# MPeV6.net
KiCad netlist of a schematic drawn in EAGLE
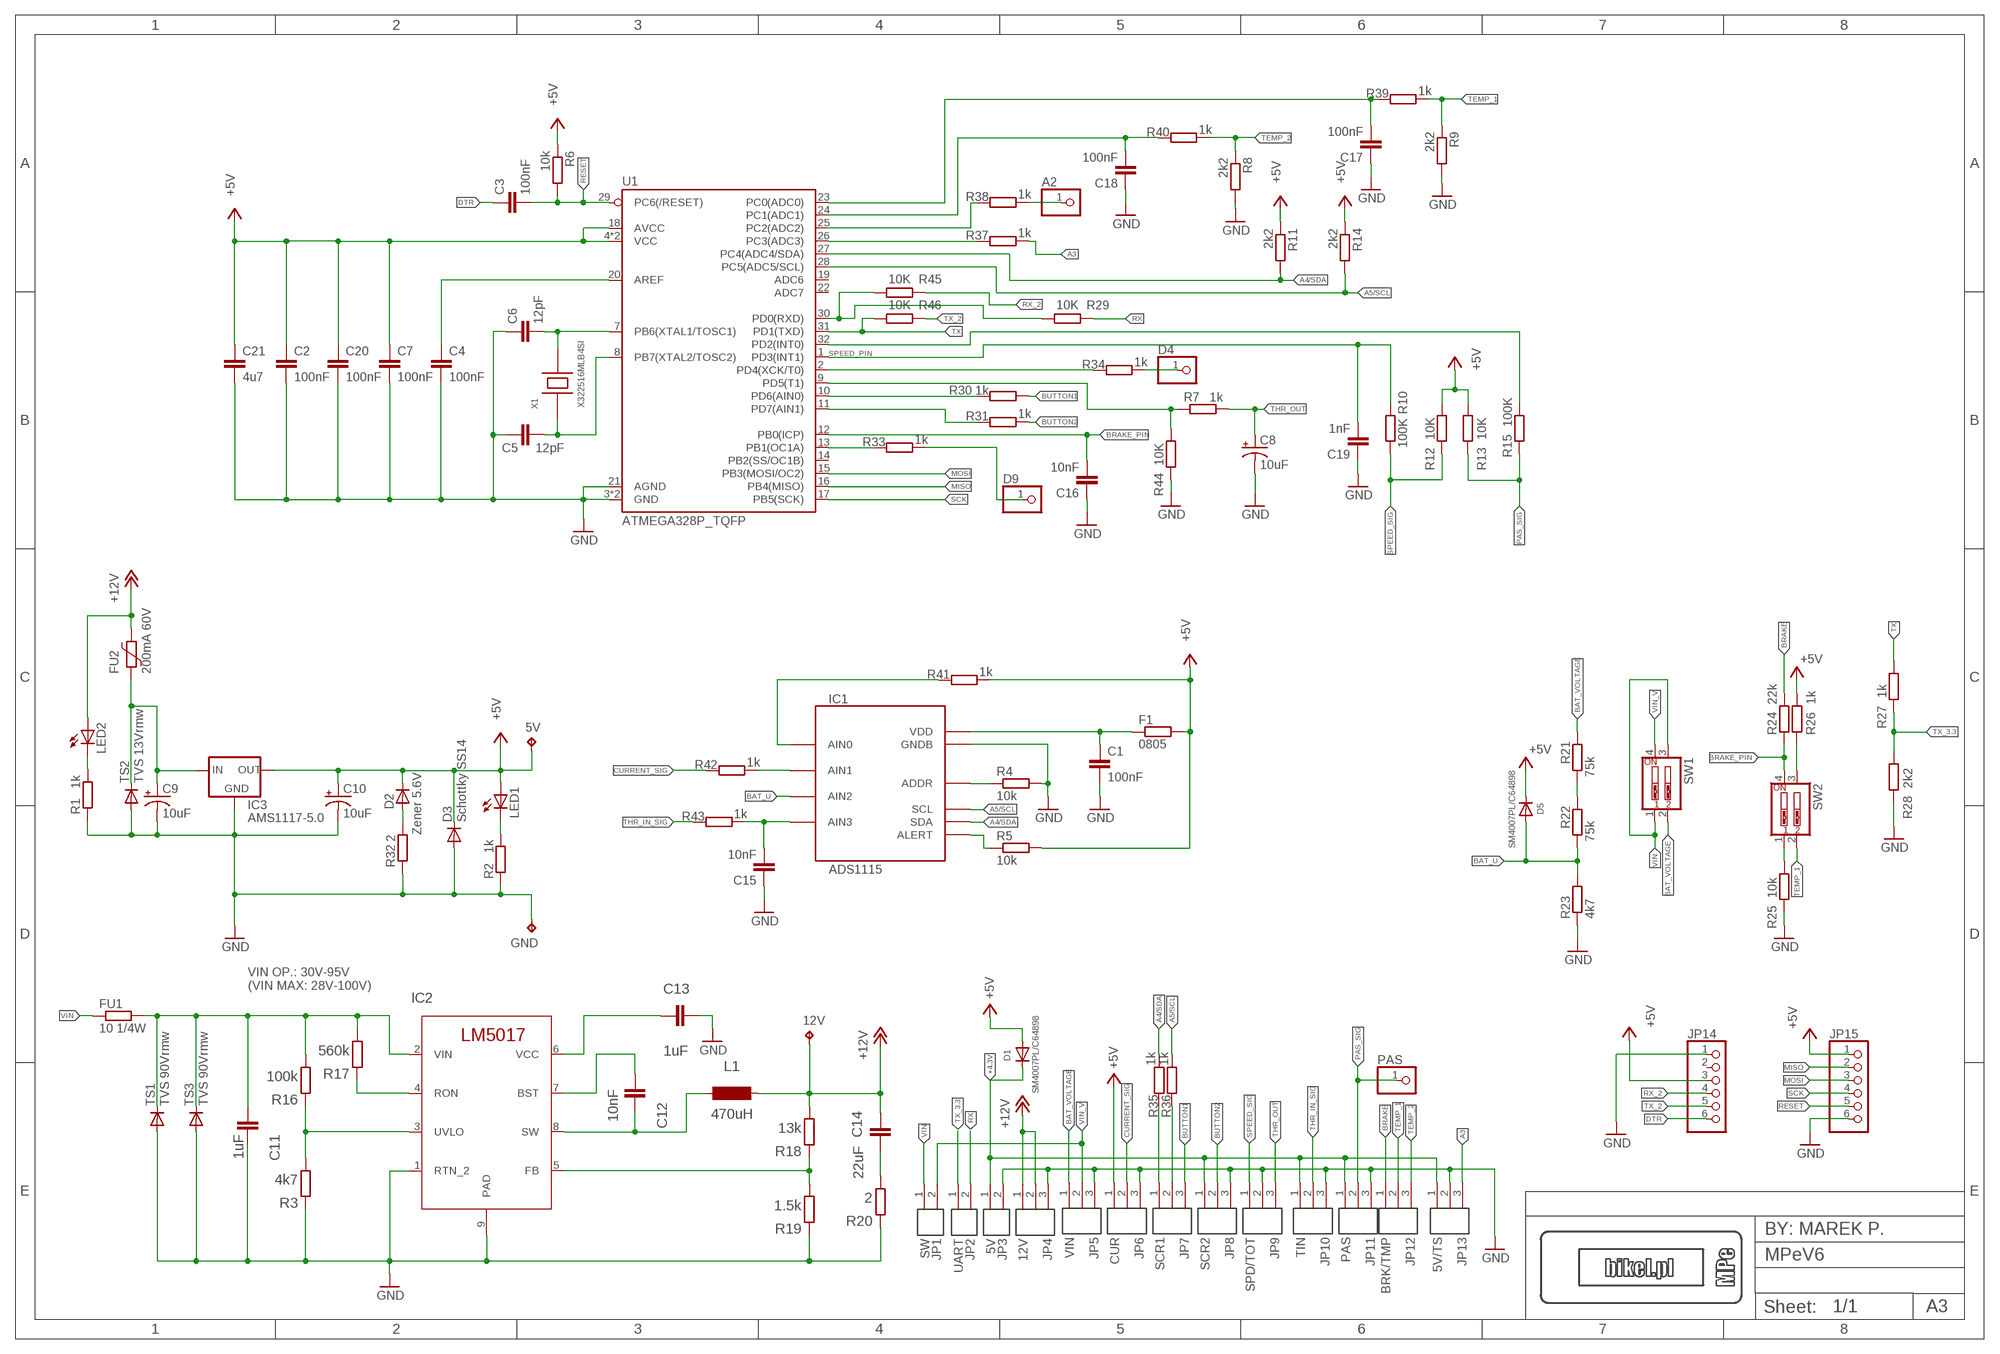
[diagram p0: schematic, sheet 1]

(export (version "E")
  (design (tool "Eeschema 10.0.6"))
  (components
    (comp (ref "5V")
      (value "TP_5V")
      (footprint "eagle-import:P1-13")
      (libsource (lib "eagle-import") (part "TPPAD1-13"))
    )
    (comp (ref "12V")
      (value "TP_5V")
      (footprint "eagle-import:P1-13")
      (libsource (lib "eagle-import") (part "TPPAD1-13"))
    )
    (comp (ref "A2")
      (value "PINHD-1X1")
      (footprint "eagle-import:1X01")
      (libsource (lib "eagle-import") (part "PINHD-1X1"))
    )
    (comp (ref "C1")
      (value "100nF")
      (footprint "eagle-import:C0603")
      (libsource (lib "eagle-import") (part "C-EUC0603"))
    )
    (comp (ref "C2")
      (value "100nF")
      (footprint "eagle-import:C0603")
      (libsource (lib "eagle-import") (part "C-EUC0603"))
    )
    (comp (ref "C3")
      (value "100nF")
      (footprint "eagle-import:C0603")
      (libsource (lib "eagle-import") (part "C-EUC0603"))
    )
    (comp (ref "C4")
      (value "100nF")
      (footprint "eagle-import:C0603")
      (libsource (lib "eagle-import") (part "C-EUC0603"))
    )
    (comp (ref "C5")
      (value "12pF")
      (footprint "eagle-import:C0603")
      (libsource (lib "eagle-import") (part "C-EUC0603"))
    )
    (comp (ref "C6")
      (value "12pF")
      (footprint "eagle-import:C0603")
      (libsource (lib "eagle-import") (part "C-EUC0603"))
    )
    (comp (ref "C7")
      (value "100nF")
      (footprint "eagle-import:C0603")
      (libsource (lib "eagle-import") (part "C-EUC0603"))
    )
    (comp (ref "C8")
      (value "10uF")
      (footprint "eagle-import:EIA3216")
      (libsource (lib "eagle-import") (part "10UF-POLAR-EIA3216-16V-10%(TANT)"))
    )
    (comp (ref "C9")
      (value "10uF")
      (footprint "eagle-import:EIA3216")
      (libsource (lib "eagle-import") (part "10UF-POLAR-EIA3216-16V-10%(TANT)"))
    )
    (comp (ref "C10")
      (value "10uF")
      (footprint "eagle-import:EIA3216")
      (libsource (lib "eagle-import") (part "10UF-POLAR-EIA3216-16V-10%(TANT)"))
    )
    (comp (ref "C11")
      (value "1uF")
      (footprint "eagle-import:C1206")
      (libsource (lib "eagle-import") (part "C-EUC1206"))
    )
    (comp (ref "C12")
      (value "10nF")
      (footprint "eagle-import:C0805")
      (libsource (lib "eagle-import") (part "C-EUC0805"))
    )
    (comp (ref "C13")
      (value "1uF")
      (footprint "eagle-import:C0603")
      (libsource (lib "eagle-import") (part "C-EUC0603"))
    )
    (comp (ref "C14")
      (value "22uF")
      (footprint "eagle-import:C0805")
      (libsource (lib "eagle-import") (part "C-EUC0805"))
    )
    (comp (ref "C15")
      (value "10nF")
      (footprint "eagle-import:C0603")
      (libsource (lib "eagle-import") (part "C-EUC0603"))
    )
    (comp (ref "C16")
      (value "10nF")
      (footprint "eagle-import:C0603")
      (libsource (lib "eagle-import") (part "C-EUC0603"))
    )
    (comp (ref "C17")
      (value "100nF")
      (footprint "eagle-import:C0603")
      (libsource (lib "eagle-import") (part "C-EUC0603"))
    )
    (comp (ref "C18")
      (value "100nF")
      (footprint "eagle-import:C0603")
      (libsource (lib "eagle-import") (part "C-EUC0603"))
    )
    (comp (ref "C19")
      (value "1nF")
      (footprint "eagle-import:C0603")
      (libsource (lib "eagle-import") (part "C-EUC0603"))
    )
    (comp (ref "C20")
      (value "100nF")
      (footprint "eagle-import:C0603")
      (libsource (lib "eagle-import") (part "C-EUC0603"))
    )
    (comp (ref "C21")
      (value "4u7")
      (footprint "eagle-import:C0603")
      (libsource (lib "eagle-import") (part "C-EUC0603"))
    )
    (comp (ref "D1")
      (value "SM4007PL/C64898")
      (footprint "eagle-import:SOD-123")
      (libsource (lib "eagle-import") (part "DIODESOD-123"))
    )
    (comp (ref "D2")
      (value "Zener 5.6V")
      (footprint "eagle-import:MELF-MLL34")
      (libsource (lib "eagle-import") (part "D-MLL-34"))
    )
    (comp (ref "D3")
      (value "Schottky SS14")
      (footprint "eagle-import:DO-214AC")
      (libsource (lib "eagle-import") (part "DIODE-DO-214AC"))
    )
    (comp (ref "D4")
      (value "PINHD-1X1")
      (footprint "eagle-import:1X01")
      (libsource (lib "eagle-import") (part "PINHD-1X1"))
    )
    (comp (ref "D5")
      (value "SM4007PL/C64898")
      (footprint "eagle-import:SOD-123")
      (libsource (lib "eagle-import") (part "DIODESOD-123"))
    )
    (comp (ref "D9")
      (value "PINHD-1X1")
      (footprint "eagle-import:1X01")
      (libsource (lib "eagle-import") (part "PINHD-1X1"))
    )
    (comp (ref "F1")
      (value "0805")
      (footprint "eagle-import:R0805")
      (libsource (lib "eagle-import") (part "R-EU_R0805"))
    )
    (comp (ref "FU1")
      (value "10 1/4W")
      (footprint "eagle-import:0204_7")
      (libsource (lib "eagle-import") (part "R-EU_0204/7"))
    )
    (comp (ref "FU2")
      (value "200mA 60V")
      (footprint "eagle-import:1812L")
      (fields (field (name "MF") "Littelfuse") (field (name "MPN") "1812L050/30"))
      (libsource (lib "eagle-import") (part "?1812L050/30"))
    )
    (comp (ref "GND")
      (value "TP_5V")
      (footprint "eagle-import:P1-13")
      (libsource (lib "eagle-import") (part "TPPAD1-13"))
    )
    (comp (ref "IC1")
      (value "ADS1115")
      (footprint "eagle-import:MSOP10_0.5")
      (libsource (lib "eagle-import") (part "ADS1015IDGT"))
    )
    (comp (ref "IC2")
      (value "LM5017MR/NOPB")
      (footprint "eagle-import:MRA08A")
      (fields (field (name "MANUFACTURER_PART_NUMBER") "LM5017MRNOPB"))
      (libsource (lib "eagle-import") (part "LM5017MR/NOPB"))
    )
    (comp (ref "IC3")
      (value "AMS1117-5.0")
      (footprint "eagle-import:SOT223")
      (fields (field (name "MF") "Texas Instruments") (field (name "MPN") "LM1117MP-5.0"))
      (libsource (lib "eagle-import") (part "LM1117?-MP5.0"))
    )
    (comp (ref "JP1")
      (value "SW")
      (footprint "eagle-import:ARK254-PB+")
      (libsource (lib "eagle-import") (part "ARK254-2PB+"))
    )
    (comp (ref "JP2")
      (value "UART")
      (footprint "eagle-import:ARK254-2-COM")
      (libsource (lib "eagle-import") (part "ARK254-2ARK254-2-COM"))
    )
    (comp (ref "JP3")
      (value "5V")
      (footprint "eagle-import:ARK254-2-5V")
      (libsource (lib "eagle-import") (part "ARK254-2ARK254-2-5V"))
    )
    (comp (ref "JP4")
      (value "12V")
      (footprint "eagle-import:ARK254-3-12V-EL")
      (libsource (lib "eagle-import") (part "ARK254-3ARK254-3-12V-EL"))
    )
    (comp (ref "JP5")
      (value "VIN")
      (footprint "eagle-import:ARK254-3-VIN")
      (libsource (lib "eagle-import") (part "ARK254-3ARK254-3-VIN"))
    )
    (comp (ref "JP6")
      (value "CUR")
      (footprint "eagle-import:ARK254-3+S-")
      (libsource (lib "eagle-import") (part "ARK254-3+S-"))
    )
    (comp (ref "JP7")
      (value "SCR1")
      (footprint "eagle-import:ARK254-3")
      (libsource (lib "eagle-import") (part "ARK254-3"))
    )
    (comp (ref "JP8")
      (value "SCR2")
      (footprint "eagle-import:ARK254-3")
      (libsource (lib "eagle-import") (part "ARK254-3"))
    )
    (comp (ref "JP9")
      (value "SPD/TOT")
      (footprint "eagle-import:ARK254-3-SPD-TOT")
      (libsource (lib "eagle-import") (part "ARK254-3ARK254-3-SPD-TOT"))
    )
    (comp (ref "JP10")
      (value "TIN")
      (footprint "eagle-import:ARK254-3+S-")
      (libsource (lib "eagle-import") (part "ARK254-3+S-"))
    )
    (comp (ref "JP11")
      (value "PAS")
      (footprint "eagle-import:ARK254-3+S-")
      (libsource (lib "eagle-import") (part "ARK254-3+S-"))
    )
    (comp (ref "JP12")
      (value "BRK/TMP")
      (footprint "eagle-import:ARK254-3-BRK-TMP")
      (libsource (lib "eagle-import") (part "ARK254-3ARK254-3-BRK-TMP"))
    )
    (comp (ref "JP13")
      (value "5V/TS")
      (footprint "eagle-import:ARK254-3-5V-TS")
      (libsource (lib "eagle-import") (part "ARK254-3ARK254-3-5V-TS"))
    )
    (comp (ref "JP14")
      (value "PINHD-1X6")
      (footprint "eagle-import:1X06")
      (libsource (lib "eagle-import") (part "PINHD-1X6"))
    )
    (comp (ref "JP15")
      (value "PINHD-1X6")
      (footprint "eagle-import:1X06")
      (libsource (lib "eagle-import") (part "PINHD-1X6"))
    )
    (comp (ref "L1")
      (value "470uH")
      (footprint "eagle-import:SLF12555T-102MR34-PF")
      (libsource (lib "eagle-import") (part "SLF12555T-102MR34-PF"))
    )
    (comp (ref "LED1")
      (value "LEDCHIP-LED0805")
      (footprint "eagle-import:CHIP-LED0805")
      (libsource (lib "eagle-import") (part "LEDCHIP-LED0805"))
    )
    (comp (ref "LED2")
      (value "LEDCHIP-LED0805")
      (footprint "eagle-import:CHIP-LED0805")
      (libsource (lib "eagle-import") (part "LEDCHIP-LED0805"))
    )
    (comp (ref "PAS")
      (value "PINHD-1X1")
      (footprint "eagle-import:1X01")
      (libsource (lib "eagle-import") (part "PINHD-1X1"))
    )
    (comp (ref "R1")
      (value "1k")
      (footprint "eagle-import:R0603")
      (libsource (lib "eagle-import") (part "R-EU_R0603"))
    )
    (comp (ref "R2")
      (value "1k")
      (footprint "eagle-import:R0603")
      (libsource (lib "eagle-import") (part "R-EU_R0603"))
    )
    (comp (ref "R3")
      (value "4k7")
      (footprint "eagle-import:R0603")
      (libsource (lib "eagle-import") (part "R-EU_R0603"))
    )
    (comp (ref "R4")
      (value "10k")
      (footprint "eagle-import:R0603")
      (libsource (lib "eagle-import") (part "R-EU_R0603"))
    )
    (comp (ref "R5")
      (value "10k")
      (footprint "eagle-import:R0603")
      (libsource (lib "eagle-import") (part "R-EU_R0603"))
    )
    (comp (ref "R6")
      (value "10k")
      (footprint "eagle-import:R0603")
      (libsource (lib "eagle-import") (part "R-EU_R0603"))
    )
    (comp (ref "R7")
      (value "1k")
      (footprint "eagle-import:R0603")
      (libsource (lib "eagle-import") (part "R-EU_R0603"))
    )
    (comp (ref "R8")
      (value "2k2")
      (footprint "eagle-import:R0603")
      (libsource (lib "eagle-import") (part "R-EU_R0603"))
    )
    (comp (ref "R9")
      (value "2k2")
      (footprint "eagle-import:R0603")
      (libsource (lib "eagle-import") (part "R-EU_R0603"))
    )
    (comp (ref "R10")
      (value "100K")
      (footprint "eagle-import:R0603")
      (libsource (lib "eagle-import") (part "R-EU_R0603"))
    )
    (comp (ref "R11")
      (value "2k2")
      (footprint "eagle-import:R0603")
      (libsource (lib "eagle-import") (part "R-EU_R0603"))
    )
    (comp (ref "R12")
      (value "10K")
      (footprint "eagle-import:R0603")
      (libsource (lib "eagle-import") (part "R-EU_R0603"))
    )
    (comp (ref "R13")
      (value "10K")
      (footprint "eagle-import:R0603")
      (libsource (lib "eagle-import") (part "R-EU_R0603"))
    )
    (comp (ref "R14")
      (value "2k2")
      (footprint "eagle-import:R0603")
      (libsource (lib "eagle-import") (part "R-EU_R0603"))
    )
    (comp (ref "R15")
      (value "100K")
      (footprint "eagle-import:R0603")
      (libsource (lib "eagle-import") (part "R-EU_R0603"))
    )
    (comp (ref "R16")
      (value "100k")
      (footprint "eagle-import:R0603")
      (libsource (lib "eagle-import") (part "R-EU_R0603"))
    )
    (comp (ref "R17")
      (value "560k")
      (footprint "eagle-import:R0603")
      (libsource (lib "eagle-import") (part "R-EU_R0603"))
    )
    (comp (ref "R18")
      (value "13k")
      (footprint "eagle-import:R0603")
      (libsource (lib "eagle-import") (part "R-EU_R0603"))
    )
    (comp (ref "R19")
      (value "1.5k")
      (footprint "eagle-import:R0603")
      (libsource (lib "eagle-import") (part "R-EU_R0603"))
    )
    (comp (ref "R20")
      (value "2")
      (footprint "eagle-import:R0805")
      (libsource (lib "eagle-import") (part "R-EU_R0805"))
    )
    (comp (ref "R21")
      (value "75k")
      (footprint "eagle-import:R0805")
      (libsource (lib "eagle-import") (part "R-EU_R0805"))
    )
    (comp (ref "R22")
      (value "75k")
      (footprint "eagle-import:R0805")
      (libsource (lib "eagle-import") (part "R-EU_R0805"))
    )
    (comp (ref "R23")
      (value "4k7")
      (footprint "eagle-import:R0805")
      (libsource (lib "eagle-import") (part "R-EU_R0805"))
    )
    (comp (ref "R24")
      (value "22k")
      (footprint "eagle-import:R0603")
      (libsource (lib "eagle-import") (part "R-EU_R0603"))
    )
    (comp (ref "R25")
      (value "10k")
      (footprint "eagle-import:R0603")
      (libsource (lib "eagle-import") (part "R-EU_R0603"))
    )
    (comp (ref "R26")
      (value "1k")
      (footprint "eagle-import:R0603")
      (libsource (lib "eagle-import") (part "R-EU_R0603"))
    )
    (comp (ref "R27")
      (value "1k")
      (footprint "eagle-import:R0603")
      (libsource (lib "eagle-import") (part "R-EU_R0603"))
    )
    (comp (ref "R28")
      (value "2k2")
      (footprint "eagle-import:R0603")
      (libsource (lib "eagle-import") (part "R-EU_R0603"))
    )
    (comp (ref "R29")
      (value "10K")
      (footprint "eagle-import:R0603")
      (libsource (lib "eagle-import") (part "R-EU_R0603"))
    )
    (comp (ref "R30")
      (value "1k")
      (footprint "eagle-import:R0603")
      (libsource (lib "eagle-import") (part "R-EU_R0603"))
    )
    (comp (ref "R31")
      (value "1k")
      (footprint "eagle-import:R0603")
      (libsource (lib "eagle-import") (part "R-EU_R0603"))
    )
    (comp (ref "R32")
      (value "2")
      (footprint "eagle-import:R0805")
      (libsource (lib "eagle-import") (part "R-EU_R0805"))
    )
    (comp (ref "R33")
      (value "1k")
      (footprint "eagle-import:R0603")
      (libsource (lib "eagle-import") (part "R-EU_R0603"))
    )
    (comp (ref "R34")
      (value "1k")
      (footprint "eagle-import:R0603")
      (libsource (lib "eagle-import") (part "R-EU_R0603"))
    )
    (comp (ref "R35")
      (value "1k")
      (footprint "eagle-import:R0603")
      (libsource (lib "eagle-import") (part "R-EU_R0603"))
    )
    (comp (ref "R36")
      (value "1k")
      (footprint "eagle-import:R0603")
      (libsource (lib "eagle-import") (part "R-EU_R0603"))
    )
    (comp (ref "R37")
      (value "1k")
      (footprint "eagle-import:R0603")
      (libsource (lib "eagle-import") (part "R-EU_R0603"))
    )
    (comp (ref "R38")
      (value "1k")
      (footprint "eagle-import:R0603")
      (libsource (lib "eagle-import") (part "R-EU_R0603"))
    )
    (comp (ref "R39")
      (value "1k")
      (footprint "eagle-import:R0603")
      (libsource (lib "eagle-import") (part "R-EU_R0603"))
    )
    (comp (ref "R40")
      (value "1k")
      (footprint "eagle-import:R0603")
      (libsource (lib "eagle-import") (part "R-EU_R0603"))
    )
    (comp (ref "R41")
      (value "1k")
      (footprint "eagle-import:R0603")
      (libsource (lib "eagle-import") (part "R-EU_R0603"))
    )
    (comp (ref "R42")
      (value "1k")
      (footprint "eagle-import:R0603")
      (libsource (lib "eagle-import") (part "R-EU_R0603"))
    )
    (comp (ref "R43")
      (value "1k")
      (footprint "eagle-import:R0603")
      (libsource (lib "eagle-import") (part "R-EU_R0603"))
    )
    (comp (ref "R44")
      (value "10K")
      (footprint "eagle-import:R0603")
      (libsource (lib "eagle-import") (part "R-EU_R0603"))
    )
    (comp (ref "R45")
      (value "10K")
      (footprint "eagle-import:R0603")
      (libsource (lib "eagle-import") (part "R-EU_R0603"))
    )
    (comp (ref "R46")
      (value "10K")
      (footprint "eagle-import:R0603")
      (libsource (lib "eagle-import") (part "R-EU_R0603"))
    )
    (comp (ref "SW1")
      (value "SW_DIP-2")
      (footprint "eagle-import:EDG-02")
      (libsource (lib "eagle-import") (part "SW_DIP-2"))
    )
    (comp (ref "SW2")
      (value "SW_DIP-2")
      (footprint "eagle-import:EDG-02")
      (libsource (lib "eagle-import") (part "SW_DIP-2"))
    )
    (comp (ref "TS1")
      (value "TVS 90Vrmw")
      (footprint "eagle-import:DO214AA")
      (fields (field (name "MF") "Fairchild") (field (name "MPN") "S2A"))
      (libsource (lib "eagle-import") (part "S2A"))
    )
    (comp (ref "TS2")
      (value "TVS 13Vrmw")
      (footprint "eagle-import:DO214AA")
      (fields (field (name "MF") "Fairchild") (field (name "MPN") "S2A"))
      (libsource (lib "eagle-import") (part "S2A"))
    )
    (comp (ref "TS3")
      (value "TVS 90Vrmw")
      (footprint "eagle-import:DO214AA")
      (fields (field (name "MF") "Fairchild") (field (name "MPN") "S2A"))
      (libsource (lib "eagle-import") (part "S2A"))
    )
    (comp (ref "U1")
      (value "ATMEGA328P_TQFP")
      (footprint "eagle-import:TQFP32-08")
      (libsource (lib "eagle-import") (part "ATMEGA328P_TQFP"))
    )
    (comp (ref "X1")
      (value "X322516MLB4SI")
      (footprint "eagle-import:IQG3225")
      (libsource (lib "eagle-import") (part "SMAC-3225"))
    )
  )
  (nets
    (net (code "1") (name "+4.3V") (class "Default")
      (node (ref "D1") (pin "C") (pinfunction "C_C") (pintype "passive"))
      (node (ref "JP10") (pin "1") (pinfunction "1_1") (pintype "bidirectional"))
      (node (ref "JP11") (pin "1") (pinfunction "1_1") (pintype "bidirectional"))
      (node (ref "JP13") (pin "1") (pinfunction "1_1") (pintype "bidirectional"))
      (node (ref "JP3") (pin "1") (pinfunction "1_1") (pintype "bidirectional"))
      (node (ref "JP8") (pin "1") (pinfunction "1_1") (pintype "bidirectional"))
    )
    (net (code "2") (name "+5V") (class "Default")
      (node (ref "5V") (pin "TP") (pinfunction "TP_TP") (pintype "input"))
      (node (ref "C10") (pin "+") (pinfunction "+_+") (pintype "passive"))
      (node (ref "C2") (pin "1") (pinfunction "1_1") (pintype "passive"))
      (node (ref "C20") (pin "1") (pinfunction "1_1") (pintype "passive"))
      (node (ref "C21") (pin "1") (pinfunction "1_1") (pintype "passive"))
      (node (ref "C7") (pin "1") (pinfunction "1_1") (pintype "passive"))
      (node (ref "D1") (pin "A") (pinfunction "A_A") (pintype "passive"))
      (node (ref "D2") (pin "1") (pinfunction "C_1") (pintype "passive"))
      (node (ref "D3") (pin "C") (pinfunction "C_C") (pintype "passive"))
      (node (ref "D5") (pin "C") (pinfunction "C_C") (pintype "passive"))
      (node (ref "F1") (pin "2") (pinfunction "2_2") (pintype "passive"))
      (node (ref "IC3") (pin "2") (pinfunction "OUT_2") (pintype "passive"))
      (node (ref "IC3") (pin "4") (pinfunction "OUT_4") (pintype "passive"))
      (node (ref "JP14") (pin "3") (pinfunction "3_3") (pintype "passive"))
      (node (ref "JP15") (pin "1") (pinfunction "1_1") (pintype "passive"))
      (node (ref "JP6") (pin "1") (pinfunction "1_1") (pintype "bidirectional"))
      (node (ref "LED1") (pin "A") (pinfunction "A_A") (pintype "passive"))
      (node (ref "R11") (pin "1") (pinfunction "1_1") (pintype "passive"))
      (node (ref "R12") (pin "2") (pinfunction "2_2") (pintype "passive"))
      (node (ref "R13") (pin "2") (pinfunction "2_2") (pintype "passive"))
      (node (ref "R14") (pin "1") (pinfunction "1_1") (pintype "passive"))
      (node (ref "R26") (pin "2") (pinfunction "2_2") (pintype "passive"))
      (node (ref "R41") (pin "1") (pinfunction "1_1") (pintype "passive"))
      (node (ref "R5") (pin "2") (pinfunction "2_2") (pintype "passive"))
      (node (ref "R6") (pin "1") (pinfunction "1_1") (pintype "passive"))
      (node (ref "U1") (pin "18") (pinfunction "AVCC_18") (pintype "bidirectional"))
      (node (ref "U1") (pin "4") (pinfunction "VCC_4") (pintype "bidirectional"))
      (node (ref "U1") (pin "6") (pinfunction "VCC_6") (pintype "bidirectional"))
    )
    (net (code "3") (name "+12V") (class "Default")
      (node (ref "12V") (pin "TP") (pinfunction "TP_TP") (pintype "input"))
      (node (ref "C14") (pin "1") (pinfunction "1_1") (pintype "passive"))
      (node (ref "FU2") (pin "1") (pinfunction "1_1") (pintype "passive"))
      (node (ref "JP4") (pin "1") (pinfunction "1_1") (pintype "bidirectional"))
      (node (ref "JP4") (pin "2") (pinfunction "2_2") (pintype "bidirectional"))
      (node (ref "L1") (pin "P$2") (pinfunction "2_P$2") (pintype "passive"))
      (node (ref "LED2") (pin "A") (pinfunction "A_A") (pintype "passive"))
      (node (ref "R18") (pin "1") (pinfunction "1_1") (pintype "passive"))
    )
    (net (code "4") (name "/SPEED_PIN") (class "Default")
      (node (ref "C19") (pin "2") (pinfunction "2_2") (pintype "passive"))
      (node (ref "R10") (pin "2") (pinfunction "2_2") (pintype "passive"))
      (node (ref "U1") (pin "1") (pinfunction "PD3(INT1)_1") (pintype "bidirectional"))
    )
    (net (code "5") (name "A3") (class "Default")
      (node (ref "JP13") (pin "3") (pinfunction "3_3") (pintype "bidirectional"))
      (node (ref "R37") (pin "1") (pinfunction "1_1") (pintype "passive"))
    )
    (net (code "6") (name "A4{slash}SDA") (class "Default")
      (node (ref "IC1") (pin "9") (pinfunction "SDA_9") (pintype "bidirectional"))
      (node (ref "R11") (pin "2") (pinfunction "2_2") (pintype "passive"))
      (node (ref "R35") (pin "1") (pinfunction "1_1") (pintype "passive"))
      (node (ref "U1") (pin "27") (pinfunction "PC4(ADC4/SDA)_27") (pintype "bidirectional"))
    )
    (net (code "7") (name "A5{slash}SCL") (class "Default")
      (node (ref "IC1") (pin "10") (pinfunction "SCL_10") (pintype "bidirectional"))
      (node (ref "R14") (pin "2") (pinfunction "2_2") (pintype "passive"))
      (node (ref "R36") (pin "1") (pinfunction "1_1") (pintype "passive"))
      (node (ref "U1") (pin "28") (pinfunction "PC5(ADC5/SCL)_28") (pintype "bidirectional"))
    )
    (net (code "8") (name "BAT_U") (class "Default")
      (node (ref "D5") (pin "A") (pinfunction "A_A") (pintype "passive"))
      (node (ref "IC1") (pin "6") (pinfunction "AIN2_6") (pintype "input"))
      (node (ref "R22") (pin "1") (pinfunction "1_1") (pintype "passive"))
      (node (ref "R23") (pin "2") (pinfunction "2_2") (pintype "passive"))
    )
    (net (code "9") (name "BAT_VOLTAGE") (class "Default")
      (node (ref "JP5") (pin "1") (pinfunction "1_1") (pintype "bidirectional"))
      (node (ref "R21") (pin "2") (pinfunction "2_2") (pintype "passive"))
      (node (ref "SW1") (pin "2") (pinfunction "2_2") (pintype "passive"))
    )
    (net (code "10") (name "BRAKE") (class "Default")
      (node (ref "JP12") (pin "1") (pinfunction "1_1") (pintype "bidirectional"))
      (node (ref "R24") (pin "2") (pinfunction "2_2") (pintype "passive"))
    )
    (net (code "11") (name "BRAKE_PIN") (class "Default")
      (node (ref "C16") (pin "2") (pinfunction "2_2") (pintype "passive"))
      (node (ref "R24") (pin "1") (pinfunction "1_1") (pintype "passive"))
      (node (ref "SW2") (pin "4") (pinfunction "4_4") (pintype "passive"))
      (node (ref "U1") (pin "12") (pinfunction "PB0(ICP)_12") (pintype "bidirectional"))
    )
    (net (code "12") (name "BUTTON1") (class "Default")
      (node (ref "JP7") (pin "3") (pinfunction "3_3") (pintype "bidirectional"))
      (node (ref "R30") (pin "1") (pinfunction "1_1") (pintype "passive"))
    )
    (net (code "13") (name "BUTTON2") (class "Default")
      (node (ref "JP8") (pin "2") (pinfunction "2_2") (pintype "bidirectional"))
      (node (ref "R31") (pin "1") (pinfunction "1_1") (pintype "passive"))
    )
    (net (code "14") (name "CURRENT_SIG") (class "Default")
      (node (ref "JP6") (pin "2") (pinfunction "2_2") (pintype "bidirectional"))
      (node (ref "R42") (pin "2") (pinfunction "2_2") (pintype "passive"))
    )
    (net (code "15") (name "DTR") (class "Default")
      (node (ref "C3") (pin "1") (pinfunction "1_1") (pintype "passive"))
      (node (ref "JP14") (pin "6") (pinfunction "6_6") (pintype "passive"))
    )
    (net (code "16") (name "GND") (class "Default")
      (node (ref "C1") (pin "2") (pinfunction "2_2") (pintype "passive"))
      (node (ref "C10") (pin "-") (pinfunction "-_-") (pintype "passive"))
      (node (ref "C11") (pin "2") (pinfunction "2_2") (pintype "passive"))
      (node (ref "C13") (pin "1") (pinfunction "1_1") (pintype "passive"))
      (node (ref "C15") (pin "1") (pinfunction "1_1") (pintype "passive"))
      (node (ref "C16") (pin "1") (pinfunction "1_1") (pintype "passive"))
      (node (ref "C17") (pin "1") (pinfunction "1_1") (pintype "passive"))
      (node (ref "C18") (pin "1") (pinfunction "1_1") (pintype "passive"))
      (node (ref "C19") (pin "1") (pinfunction "1_1") (pintype "passive"))
      (node (ref "C2") (pin "2") (pinfunction "2_2") (pintype "passive"))
      (node (ref "C20") (pin "2") (pinfunction "2_2") (pintype "passive"))
      (node (ref "C21") (pin "2") (pinfunction "2_2") (pintype "passive"))
      (node (ref "C4") (pin "2") (pinfunction "2_2") (pintype "passive"))
      (node (ref "C5") (pin "1") (pinfunction "1_1") (pintype "passive"))
      (node (ref "C6") (pin "1") (pinfunction "1_1") (pintype "passive"))
      (node (ref "C7") (pin "2") (pinfunction "2_2") (pintype "passive"))
      (node (ref "C8") (pin "-") (pinfunction "-_-") (pintype "passive"))
      (node (ref "C9") (pin "-") (pinfunction "-_-") (pintype "passive"))
      (node (ref "D3") (pin "A") (pinfunction "A_A") (pintype "passive"))
      (node (ref "GND") (pin "TP") (pinfunction "TP_TP") (pintype "input"))
      (node (ref "IC1") (pin "3") (pinfunction "GNDB_3") (pintype "power_in"))
      (node (ref "IC2") (pin "1") (pinfunction "RTN_2_1") (pintype "passive"))
      (node (ref "IC2") (pin "9") (pinfunction "PAD_9") (pintype "bidirectional"))
      (node (ref "IC3") (pin "1") (pinfunction "GND_1") (pintype "input"))
      (node (ref "JP10") (pin "3") (pinfunction "3_3") (pintype "bidirectional"))
      (node (ref "JP11") (pin "3") (pinfunction "3_3") (pintype "bidirectional"))
      (node (ref "JP13") (pin "2") (pinfunction "2_2") (pintype "bidirectional"))
      (node (ref "JP14") (pin "1") (pinfunction "1_1") (pintype "passive"))
      (node (ref "JP15") (pin "6") (pinfunction "6_6") (pintype "passive"))
      (node (ref "JP3") (pin "2") (pinfunction "2_2") (pintype "bidirectional"))
      (node (ref "JP4") (pin "3") (pinfunction "3_3") (pintype "bidirectional"))
      (node (ref "JP5") (pin "3") (pinfunction "3_3") (pintype "bidirectional"))
      (node (ref "JP6") (pin "3") (pinfunction "3_3") (pintype "bidirectional"))
      (node (ref "JP8") (pin "3") (pinfunction "3_3") (pintype "bidirectional"))
      (node (ref "JP9") (pin "2") (pinfunction "2_2") (pintype "bidirectional"))
      (node (ref "R1") (pin "1") (pinfunction "1_1") (pintype "passive"))
      (node (ref "R19") (pin "2") (pinfunction "2_2") (pintype "passive"))
      (node (ref "R2") (pin "1") (pinfunction "1_1") (pintype "passive"))
      (node (ref "R20") (pin "2") (pinfunction "2_2") (pintype "passive"))
      (node (ref "R23") (pin "1") (pinfunction "1_1") (pintype "passive"))
      (node (ref "R25") (pin "1") (pinfunction "1_1") (pintype "passive"))
      (node (ref "R28") (pin "1") (pinfunction "1_1") (pintype "passive"))
      (node (ref "R3") (pin "2") (pinfunction "2_2") (pintype "passive"))
      (node (ref "R32") (pin "1") (pinfunction "1_1") (pintype "passive"))
      (node (ref "R4") (pin "2") (pinfunction "2_2") (pintype "passive"))
      (node (ref "R44") (pin "1") (pinfunction "1_1") (pintype "passive"))
      (node (ref "R8") (pin "2") (pinfunction "2_2") (pintype "passive"))
      (node (ref "R9") (pin "2") (pinfunction "2_2") (pintype "passive"))
      (node (ref "TS1") (pin "A") (pinfunction "A_A") (pintype "passive"))
      (node (ref "TS2") (pin "A") (pinfunction "A_A") (pintype "passive"))
      (node (ref "TS3") (pin "A") (pinfunction "A_A") (pintype "passive"))
      (node (ref "U1") (pin "21") (pinfunction "AGND_21") (pintype "bidirectional"))
      (node (ref "U1") (pin "3") (pinfunction "GND_3") (pintype "bidirectional"))
      (node (ref "U1") (pin "5") (pinfunction "GND_5") (pintype "bidirectional"))
    )
    (net (code "17") (name "MISO") (class "Default")
      (node (ref "JP15") (pin "2") (pinfunction "2_2") (pintype "passive"))
      (node (ref "U1") (pin "16") (pinfunction "PB4(MISO)_16") (pintype "bidirectional"))
    )
    (net (code "18") (name "MOSI") (class "Default")
      (node (ref "JP15") (pin "3") (pinfunction "3_3") (pintype "passive"))
      (node (ref "U1") (pin "15") (pinfunction "PB3(MOSI/OC2)_15") (pintype "bidirectional"))
    )
    (net (code "19") (name "Net-(A2-Pad1)") (class "Default")
      (node (ref "A2") (pin "1") (pinfunction "1_1") (pintype "passive"))
      (node (ref "R38") (pin "1") (pinfunction "1_1") (pintype "passive"))
    )
    (net (code "20") (name "Net-(C14-Pad2)") (class "Default")
      (node (ref "C14") (pin "2") (pinfunction "2_2") (pintype "passive"))
      (node (ref "R20") (pin "1") (pinfunction "1_1") (pintype "passive"))
    )
    (net (code "21") (name "Net-(D2-A)") (class "Default")
      (node (ref "D2") (pin "2") (pinfunction "A_2") (pintype "passive"))
      (node (ref "R32") (pin "2") (pinfunction "2_2") (pintype "passive"))
    )
    (net (code "22") (name "Net-(D4-Pad1)") (class "Default")
      (node (ref "D4") (pin "1") (pinfunction "1_1") (pintype "passive"))
      (node (ref "R34") (pin "1") (pinfunction "1_1") (pintype "passive"))
    )
    (net (code "23") (name "Net-(D9-Pad1)") (class "Default")
      (node (ref "D9") (pin "1") (pinfunction "1_1") (pintype "passive"))
      (node (ref "R33") (pin "1") (pinfunction "1_1") (pintype "passive"))
    )
    (net (code "24") (name "Net-(IC1-ADDR)") (class "Default")
      (node (ref "IC1") (pin "1") (pinfunction "ADDR_1") (pintype "input"))
      (node (ref "R4") (pin "1") (pinfunction "1_1") (pintype "passive"))
    )
    (net (code "25") (name "Net-(IC1-AIN0)") (class "Default")
      (node (ref "IC1") (pin "4") (pinfunction "AIN0_4") (pintype "input"))
      (node (ref "R41") (pin "2") (pinfunction "2_2") (pintype "passive"))
    )
    (net (code "26") (name "Net-(IC1-AIN1)") (class "Default")
      (node (ref "IC1") (pin "5") (pinfunction "AIN1_5") (pintype "input"))
      (node (ref "R42") (pin "1") (pinfunction "1_1") (pintype "passive"))
    )
    (net (code "27") (name "Net-(IC1-AIN3)") (class "Default")
      (node (ref "C15") (pin "2") (pinfunction "2_2") (pintype "passive"))
      (node (ref "IC1") (pin "7") (pinfunction "AIN3_7") (pintype "input"))
      (node (ref "R43") (pin "1") (pinfunction "1_1") (pintype "passive"))
    )
    (net (code "28") (name "Net-(IC1-ALERT)") (class "Default")
      (node (ref "IC1") (pin "2") (pinfunction "ALERT_2") (pintype "output"))
      (node (ref "R5") (pin "1") (pinfunction "1_1") (pintype "passive"))
    )
    (net (code "29") (name "Net-(IC1-VDD)") (class "Default")
      (node (ref "C1") (pin "1") (pinfunction "1_1") (pintype "passive"))
      (node (ref "F1") (pin "1") (pinfunction "1_1") (pintype "passive"))
      (node (ref "IC1") (pin "8") (pinfunction "VDD_8") (pintype "power_in"))
    )
    (net (code "30") (name "Net-(IC2-BST)") (class "Default")
      (node (ref "C12") (pin "1") (pinfunction "1_1") (pintype "passive"))
      (node (ref "IC2") (pin "7") (pinfunction "BST_7") (pintype "passive"))
    )
    (net (code "31") (name "Net-(IC2-FB)") (class "Default")
      (node (ref "IC2") (pin "5") (pinfunction "FB_5") (pintype "passive"))
      (node (ref "R18") (pin "2") (pinfunction "2_2") (pintype "passive"))
      (node (ref "R19") (pin "1") (pinfunction "1_1") (pintype "passive"))
    )
    (net (code "32") (name "Net-(IC2-RON)") (class "Default")
      (node (ref "IC2") (pin "4") (pinfunction "RON_4") (pintype "passive"))
      (node (ref "R17") (pin "2") (pinfunction "2_2") (pintype "passive"))
    )
    (net (code "33") (name "Net-(IC2-SW)") (class "Default")
      (node (ref "C12") (pin "2") (pinfunction "2_2") (pintype "passive"))
      (node (ref "IC2") (pin "8") (pinfunction "SW_8") (pintype "passive"))
      (node (ref "L1") (pin "P$1") (pinfunction "1_P$1") (pintype "passive"))
    )
    (net (code "34") (name "Net-(IC2-UVLO)") (class "Default")
      (node (ref "IC2") (pin "3") (pinfunction "UVLO_3") (pintype "passive"))
      (node (ref "R16") (pin "2") (pinfunction "2_2") (pintype "passive"))
      (node (ref "R3") (pin "1") (pinfunction "1_1") (pintype "passive"))
    )
    (net (code "35") (name "Net-(IC2-VCC)") (class "Default")
      (node (ref "C13") (pin "2") (pinfunction "2_2") (pintype "passive"))
      (node (ref "IC2") (pin "6") (pinfunction "VCC_6") (pintype "passive"))
    )
    (net (code "36") (name "Net-(IC2-VIN)") (class "Default")
      (node (ref "C11") (pin "1") (pinfunction "1_1") (pintype "passive"))
      (node (ref "FU1") (pin "2") (pinfunction "2_2") (pintype "passive"))
      (node (ref "IC2") (pin "2") (pinfunction "VIN_2") (pintype "passive"))
      (node (ref "R16") (pin "1") (pinfunction "1_1") (pintype "passive"))
      (node (ref "R17") (pin "1") (pinfunction "1_1") (pintype "passive"))
      (node (ref "TS1") (pin "C") (pinfunction "C_C") (pintype "passive"))
      (node (ref "TS3") (pin "C") (pinfunction "C_C") (pintype "passive"))
    )
    (net (code "37") (name "Net-(IC3-IN)") (class "Default")
      (node (ref "C9") (pin "+") (pinfunction "+_+") (pintype "passive"))
      (node (ref "FU2") (pin "2") (pinfunction "2_2") (pintype "passive"))
      (node (ref "IC3") (pin "3") (pinfunction "IN_3") (pintype "input"))
      (node (ref "TS2") (pin "C") (pinfunction "C_C") (pintype "passive"))
    )
    (net (code "38") (name "Net-(JP7-Pad1)") (class "Default")
      (node (ref "JP7") (pin "1") (pinfunction "1_1") (pintype "bidirectional"))
      (node (ref "R35") (pin "2") (pinfunction "2_2") (pintype "passive"))
    )
    (net (code "39") (name "Net-(JP7-Pad2)") (class "Default")
      (node (ref "JP7") (pin "2") (pinfunction "2_2") (pintype "bidirectional"))
      (node (ref "R36") (pin "2") (pinfunction "2_2") (pintype "passive"))
    )
    (net (code "40") (name "Net-(LED1-PadC)") (class "Default")
      (node (ref "LED1") (pin "C") (pinfunction "C_C") (pintype "passive"))
      (node (ref "R2") (pin "2") (pinfunction "2_2") (pintype "passive"))
    )
    (net (code "41") (name "Net-(LED2-PadC)") (class "Default")
      (node (ref "LED2") (pin "C") (pinfunction "C_C") (pintype "passive"))
      (node (ref "R1") (pin "2") (pinfunction "2_2") (pintype "passive"))
    )
    (net (code "42") (name "Net-(R21-Pad1)") (class "Default")
      (node (ref "R21") (pin "1") (pinfunction "1_1") (pintype "passive"))
      (node (ref "R22") (pin "2") (pinfunction "2_2") (pintype "passive"))
    )
    (net (code "43") (name "Net-(R25-Pad2)") (class "Default")
      (node (ref "R25") (pin "2") (pinfunction "2_2") (pintype "passive"))
      (node (ref "SW2") (pin "1") (pinfunction "1_1") (pintype "passive"))
    )
    (net (code "44") (name "Net-(R26-Pad1)") (class "Default")
      (node (ref "R26") (pin "1") (pinfunction "1_1") (pintype "passive"))
      (node (ref "SW2") (pin "3") (pinfunction "3_3") (pintype "passive"))
    )
    (net (code "45") (name "Net-(U1-AREF)") (class "Default")
      (node (ref "C4") (pin "1") (pinfunction "1_1") (pintype "passive"))
      (node (ref "U1") (pin "20") (pinfunction "AREF_20") (pintype "bidirectional"))
    )
    (net (code "46") (name "Net-(U1-PB1(OC1A))") (class "Default")
      (node (ref "R33") (pin "2") (pinfunction "2_2") (pintype "passive"))
      (node (ref "U1") (pin "13") (pinfunction "PB1(OC1A)_13") (pintype "bidirectional"))
    )
    (net (code "47") (name "Net-(U1-PB6(XTAL1{slash}TOSC1))") (class "Default")
      (node (ref "C6") (pin "2") (pinfunction "2_2") (pintype "passive"))
      (node (ref "U1") (pin "7") (pinfunction "PB6(XTAL1/TOSC1)_7") (pintype "bidirectional"))
      (node (ref "X1") (pin "3") (pinfunction "PIN2_3") (pintype "bidirectional"))
    )
    (net (code "48") (name "Net-(U1-PB7(XTAL2{slash}TOSC2))") (class "Default")
      (node (ref "C5") (pin "2") (pinfunction "2_2") (pintype "passive"))
      (node (ref "U1") (pin "8") (pinfunction "PB7(XTAL2/TOSC2)_8") (pintype "bidirectional"))
      (node (ref "X1") (pin "1") (pinfunction "PIN1_1") (pintype "bidirectional"))
    )
    (net (code "49") (name "Net-(U1-PC0(ADC0))") (class "Default")
      (node (ref "C17") (pin "2") (pinfunction "2_2") (pintype "passive"))
      (node (ref "R39") (pin "2") (pinfunction "2_2") (pintype "passive"))
      (node (ref "U1") (pin "23") (pinfunction "PC0(ADC0)_23") (pintype "bidirectional"))
    )
    (net (code "50") (name "Net-(U1-PC1(ADC1))") (class "Default")
      (node (ref "C18") (pin "2") (pinfunction "2_2") (pintype "passive"))
      (node (ref "R40") (pin "2") (pinfunction "2_2") (pintype "passive"))
      (node (ref "U1") (pin "24") (pinfunction "PC1(ADC1)_24") (pintype "bidirectional"))
    )
    (net (code "51") (name "Net-(U1-PC2(ADC2))") (class "Default")
      (node (ref "R38") (pin "2") (pinfunction "2_2") (pintype "passive"))
      (node (ref "U1") (pin "25") (pinfunction "PC2(ADC2)_25") (pintype "bidirectional"))
    )
    (net (code "52") (name "Net-(U1-PC3(ADC3))") (class "Default")
      (node (ref "R37") (pin "2") (pinfunction "2_2") (pintype "passive"))
      (node (ref "U1") (pin "26") (pinfunction "PC3(ADC3)_26") (pintype "bidirectional"))
    )
    (net (code "53") (name "Net-(U1-PD0(RXD))") (class "Default")
      (node (ref "R29") (pin "2") (pinfunction "2_2") (pintype "passive"))
      (node (ref "R45") (pin "2") (pinfunction "2_2") (pintype "passive"))
      (node (ref "U1") (pin "30") (pinfunction "PD0(RXD)_30") (pintype "bidirectional"))
    )
    (net (code "54") (name "Net-(U1-PD2(INT0))") (class "Default")
      (node (ref "R15") (pin "2") (pinfunction "2_2") (pintype "passive"))
      (node (ref "U1") (pin "32") (pinfunction "PD2(INT0)_32") (pintype "bidirectional"))
    )
    (net (code "55") (name "Net-(U1-PD4(XCK{slash}T0))") (class "Default")
      (node (ref "R34") (pin "2") (pinfunction "2_2") (pintype "passive"))
      (node (ref "U1") (pin "2") (pinfunction "PD4(XCK/T0)_2") (pintype "bidirectional"))
    )
    (net (code "56") (name "Net-(U1-PD5(T1))") (class "Default")
      (node (ref "R44") (pin "2") (pinfunction "2_2") (pintype "passive"))
      (node (ref "R7") (pin "1") (pinfunction "1_1") (pintype "passive"))
      (node (ref "U1") (pin "9") (pinfunction "PD5(T1)_9") (pintype "bidirectional"))
    )
    (net (code "57") (name "Net-(U1-PD6(AIN0))") (class "Default")
      (node (ref "R30") (pin "2") (pinfunction "2_2") (pintype "passive"))
      (node (ref "U1") (pin "10") (pinfunction "PD6(AIN0)_10") (pintype "bidirectional"))
    )
    (net (code "58") (name "Net-(U1-PD7(AIN1))") (class "Default")
      (node (ref "R31") (pin "2") (pinfunction "2_2") (pintype "passive"))
      (node (ref "U1") (pin "11") (pinfunction "PD7(AIN1)_11") (pintype "bidirectional"))
    )
    (net (code "59") (name "PAS_SIG") (class "Default")
      (node (ref "JP11") (pin "2") (pinfunction "2_2") (pintype "bidirectional"))
      (node (ref "PAS") (pin "1") (pinfunction "1_1") (pintype "passive"))
      (node (ref "R13") (pin "1") (pinfunction "1_1") (pintype "passive"))
      (node (ref "R15") (pin "1") (pinfunction "1_1") (pintype "passive"))
    )
    (net (code "60") (name "RESET") (class "Default")
      (node (ref "C3") (pin "2") (pinfunction "2_2") (pintype "passive"))
      (node (ref "JP15") (pin "5") (pinfunction "5_5") (pintype "passive"))
      (node (ref "R6") (pin "2") (pinfunction "2_2") (pintype "passive"))
      (node (ref "U1") (pin "29") (pinfunction "PC6(/RESET)_29") (pintype "bidirectional"))
    )
    (net (code "61") (name "RX") (class "Default")
      (node (ref "JP2") (pin "2") (pinfunction "2_2") (pintype "bidirectional"))
      (node (ref "R29") (pin "1") (pinfunction "1_1") (pintype "passive"))
    )
    (net (code "62") (name "RX_2") (class "Default")
      (node (ref "JP14") (pin "4") (pinfunction "4_4") (pintype "passive"))
      (node (ref "R45") (pin "1") (pinfunction "1_1") (pintype "passive"))
    )
    (net (code "63") (name "SCK") (class "Default")
      (node (ref "JP15") (pin "4") (pinfunction "4_4") (pintype "passive"))
      (node (ref "U1") (pin "17") (pinfunction "PB5(SCK)_17") (pintype "bidirectional"))
    )
    (net (code "64") (name "SPEED_SIG") (class "Default")
      (node (ref "JP9") (pin "1") (pinfunction "1_1") (pintype "bidirectional"))
      (node (ref "R10") (pin "1") (pinfunction "1_1") (pintype "passive"))
      (node (ref "R12") (pin "1") (pinfunction "1_1") (pintype "passive"))
    )
    (net (code "65") (name "TEMP_1") (class "Default")
      (node (ref "JP12") (pin "2") (pinfunction "2_2") (pintype "bidirectional"))
      (node (ref "R39") (pin "1") (pinfunction "1_1") (pintype "passive"))
      (node (ref "R9") (pin "1") (pinfunction "1_1") (pintype "passive"))
      (node (ref "SW2") (pin "2") (pinfunction "2_2") (pintype "passive"))
    )
    (net (code "66") (name "TEMP_2") (class "Default")
      (node (ref "JP12") (pin "3") (pinfunction "3_3") (pintype "bidirectional"))
      (node (ref "R40") (pin "1") (pinfunction "1_1") (pintype "passive"))
      (node (ref "R8") (pin "1") (pinfunction "1_1") (pintype "passive"))
    )
    (net (code "67") (name "THR_IN_SIG") (class "Default")
      (node (ref "JP10") (pin "2") (pinfunction "2_2") (pintype "bidirectional"))
      (node (ref "R43") (pin "2") (pinfunction "2_2") (pintype "passive"))
    )
    (net (code "68") (name "THR_OUT") (class "Default")
      (node (ref "C8") (pin "+") (pinfunction "+_+") (pintype "passive"))
      (node (ref "JP9") (pin "3") (pinfunction "3_3") (pintype "bidirectional"))
      (node (ref "R7") (pin "2") (pinfunction "2_2") (pintype "passive"))
    )
    (net (code "69") (name "TX") (class "Default")
      (node (ref "R27") (pin "2") (pinfunction "2_2") (pintype "passive"))
      (node (ref "R46") (pin "2") (pinfunction "2_2") (pintype "passive"))
      (node (ref "U1") (pin "31") (pinfunction "PD1(TXD)_31") (pintype "bidirectional"))
    )
    (net (code "70") (name "TX_2") (class "Default")
      (node (ref "JP14") (pin "5") (pinfunction "5_5") (pintype "passive"))
      (node (ref "R46") (pin "1") (pinfunction "1_1") (pintype "passive"))
    )
    (net (code "71") (name "TX_3.3") (class "Default")
      (node (ref "JP2") (pin "1") (pinfunction "1_1") (pintype "bidirectional"))
      (node (ref "R27") (pin "1") (pinfunction "1_1") (pintype "passive"))
      (node (ref "R28") (pin "2") (pinfunction "2_2") (pintype "passive"))
    )
    (net (code "72") (name "VIN") (class "Default")
      (node (ref "FU1") (pin "1") (pinfunction "1_1") (pintype "passive"))
      (node (ref "JP1") (pin "1") (pinfunction "1_1") (pintype "bidirectional"))
      (node (ref "SW1") (pin "1") (pinfunction "1_1") (pintype "passive"))
      (node (ref "SW1") (pin "3") (pinfunction "3_3") (pintype "passive"))
    )
    (net (code "73") (name "VIN_V") (class "Default")
      (node (ref "JP1") (pin "2") (pinfunction "2_2") (pintype "bidirectional"))
      (node (ref "JP5") (pin "2") (pinfunction "2_2") (pintype "bidirectional"))
      (node (ref "SW1") (pin "4") (pinfunction "4_4") (pintype "passive"))
    )
    (net (code "74") (name "unconnected-(JP14-Pad2)") (class "Default")
      (node (ref "JP14") (pin "2") (pinfunction "2_2") (pintype "passive"))
    )
    (net (code "75") (name "unconnected-(U1-ADC6-Pad19)") (class "Default")
      (node (ref "U1") (pin "19") (pinfunction "ADC6_19") (pintype "bidirectional"))
    )
    (net (code "76") (name "unconnected-(U1-ADC7-Pad22)") (class "Default")
      (node (ref "U1") (pin "22") (pinfunction "ADC7_22") (pintype "bidirectional"))
    )
    (net (code "77") (name "unconnected-(U1-PB2(SS{slash}OC1B)-Pad14)") (class "Default")
      (node (ref "U1") (pin "14") (pinfunction "PB2(SS/OC1B)_14") (pintype "bidirectional"))
    )
  )
)
